# DS131-1_0-ApH.net
KiCad netlist of a schematic drawn in Altium Designer
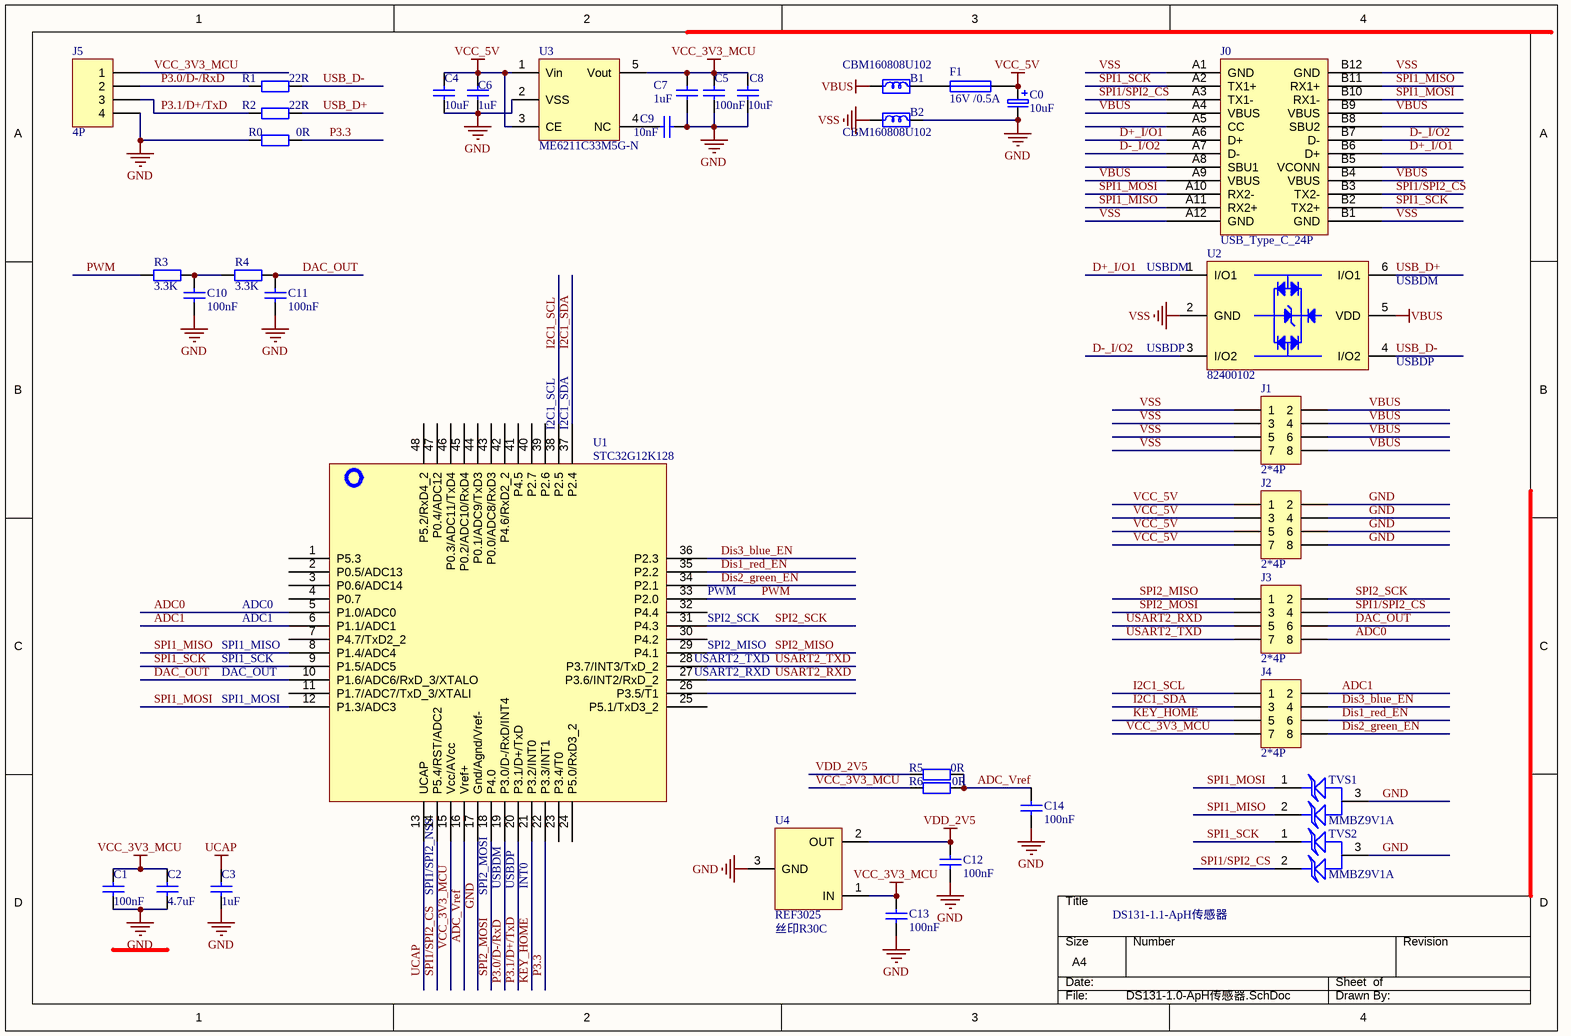
[diagram p0: DS131-1.0-ApH传感器.SchDoc]

(export (version "E")
  (design (tool "Eeschema 10.0.6"))
  (components
    (comp (ref "B1")
      (value "CBM160808U102")
      (footprint "0603Bead")
      (description "贴片磁珠")
      (libsource (lib "AD_SCH") (part "Chip Ferrite Bead 0606"))
    )
    (comp (ref "B2")
      (value "CBM160808U102")
      (footprint "0603Bead")
      (description "贴片磁珠")
      (libsource (lib "AD_SCH") (part "Chip Ferrite Bead 0606"))
    )
    (comp (ref "C0")
      (value "10uF")
      (footprint "AVX_3216-18(1206)_SMD")
      (description "钽电容")
      (fields (field (name "Comment") "AVX_10uF/16V ±10％(C106)"))
      (libsource (lib "AD_SCH") (part "AVX_10uF/16V ±10％(C106)"))
    )
    (comp (ref "C1")
      (value "100nF")
      (footprint "0603CAP")
      (description "贴片电容")
      (fields (field (name "Comment") "SMDCAP00013"))
      (libsource (lib "AD_SCH") (part "MLCC 100nF 50V ±10％ 0603"))
    )
    (comp (ref "C2")
      (value "4.7uF")
      (footprint "0603CAP")
      (description "贴片电容")
      (fields (field (name "Comment") "SMDCAP00012"))
      (libsource (lib "AD_SCH") (part "MLCC 4.7uF 50V ±10％ 0603"))
    )
    (comp (ref "C3")
      (value "1uF")
      (footprint "0603CAP")
      (description "贴片电容")
      (fields (field (name "Comment") "SMDCAP00015"))
      (libsource (lib "AD_SCH") (part "MLCC 1uF 50V ±10％ 0603"))
    )
    (comp (ref "C4")
      (value "10uF")
      (footprint "1206CAP")
      (description "贴片电容")
      (fields (field (name "Comment") "MLCC 10uF 50V ±20％ 1206"))
      (libsource (lib "AD_SCH") (part "MLCC 10uF 50V ±20％ 1206"))
    )
    (comp (ref "C5")
      (value "100nF")
      (footprint "0603CAP")
      (description "贴片电容")
      (fields (field (name "Comment") "SMDCAP00013"))
      (libsource (lib "AD_SCH") (part "MLCC 100nF 50V ±10％ 0603"))
    )
    (comp (ref "C6")
      (value "1uF")
      (footprint "0603CAP")
      (description "贴片电容")
      (fields (field (name "Comment") "SMDCAP00015"))
      (libsource (lib "AD_SCH") (part "MLCC 1uF 50V ±10％ 0603"))
    )
    (comp (ref "C7")
      (value "1uF")
      (footprint "0603CAP")
      (description "贴片电容")
      (fields (field (name "Comment") "SMDCAP00015"))
      (libsource (lib "AD_SCH") (part "MLCC 1uF 50V ±10％ 0603"))
    )
    (comp (ref "C8")
      (value "10uF")
      (footprint "1206CAP")
      (description "贴片电容")
      (fields (field (name "Comment") "MLCC 10uF 50V ±20％ 1206"))
      (libsource (lib "AD_SCH") (part "MLCC 10uF 50V ±20％ 1206"))
    )
    (comp (ref "C9")
      (value "10nF")
      (footprint "0603CAP")
      (description "贴片电容")
      (fields (field (name "Comment") "SMDCAP00010"))
      (libsource (lib "AD_SCH") (part "MLCC 10nF 50V ±10％ 0603"))
    )
    (comp (ref "C10")
      (value "100nF")
      (footprint "0603CAP")
      (description "贴片电容")
      (fields (field (name "Comment") "SMDCAP00013"))
      (libsource (lib "AD_SCH") (part "MLCC 100nF 50V ±10％ 0603"))
    )
    (comp (ref "C11")
      (value "100nF")
      (footprint "0603CAP")
      (description "贴片电容")
      (fields (field (name "Comment") "SMDCAP00013"))
      (libsource (lib "AD_SCH") (part "MLCC 100nF 50V ±10％ 0603"))
    )
    (comp (ref "C12")
      (value "100nF")
      (footprint "0603CAP")
      (description "贴片电容")
      (fields (field (name "Comment") "SMDCAP00013"))
      (libsource (lib "AD_SCH") (part "MLCC 100nF 50V ±10％ 0603"))
    )
    (comp (ref "C13")
      (value "100nF")
      (footprint "0603CAP")
      (description "贴片电容")
      (fields (field (name "Comment") "SMDCAP00013"))
      (libsource (lib "AD_SCH") (part "MLCC 100nF 50V ±10％ 0603"))
    )
    (comp (ref "C14")
      (value "100nF")
      (footprint "0603CAP")
      (description "贴片电容")
      (fields (field (name "Comment") "SMDCAP00013"))
      (libsource (lib "AD_SCH") (part "MLCC 100nF 50V ±10％ 0603"))
    )
    (comp (ref "F1")
      (value "16V /0.5A")
      (footprint "1206FUSE")
      (description "贴片自恢复保险丝 16V /0.5A")
      (fields (field (name "Comment") "SMD1206-050C-16V"))
      (libsource (lib "AD_SCH") (part "SMD1206-050C-16V"))
    )
    (comp (ref "J0")
      (value "USB_Type_C_24P")
      (footprint "USB_TYPE_C_24P_Receptacle")
      (libsource (lib "AD_SCH") (part "USB_Type_C_24P"))
    )
    (comp (ref "J1")
      (value "2*4P")
      (footprint "X1321FVS-2x04-C43D48")
      (description "双排母2x4P 立贴 1.27mm")
      (fields (field (name "Comment") "X1321FVS-2x04-C43D48"))
      (libsource (lib "AD_SCH") (part "X1321FVS-2x04-C43D48"))
    )
    (comp (ref "J2")
      (value "2*4P")
      (footprint "X1321FVS-2x04-C43D48")
      (description "双排母2x4P 立贴 1.27mm")
      (fields (field (name "Comment") "X1321FVS-2x04-C43D48"))
      (libsource (lib "AD_SCH") (part "X1321FVS-2x04-C43D48"))
    )
    (comp (ref "J3")
      (value "2*4P")
      (footprint "X1321FVS-2x04-C43D48")
      (description "双排母2x4P 立贴 1.27mm")
      (fields (field (name "Comment") "X1321FVS-2x04-C43D48"))
      (libsource (lib "AD_SCH") (part "X1321FVS-2x04-C43D48"))
    )
    (comp (ref "J4")
      (value "2*4P")
      (footprint "X1321FVS-2x04-C43D48")
      (description "双排母2x4P 立贴 1.27mm")
      (fields (field (name "Comment") "X1321FVS-2x04-C43D48"))
      (libsource (lib "AD_SCH") (part "X1321FVS-2x04-C43D48"))
    )
    (comp (ref "J5")
      (value "4P")
      (footprint "H4")
      (description "单排直针")
      (fields (field (name "Comment") "DIP4单排直针  间距2mm 针长11mm 铜"))
      (libsource (lib "AD_SCH") (part "DIP4单排直针  间距2mm 针长11mm 铜"))
    )
    (comp (ref "R0")
      (value "0R")
      (footprint "0603RES")
      (description "贴片电阻")
      (fields (field (name "Comment") "Chip 0R 1/16W ±1％ 0603"))
      (libsource (lib "AD_SCH") (part "Chip 0R 1/16W ±1％ 0603"))
    )
    (comp (ref "R1")
      (value "22R")
      (footprint "0603RES")
      (description "贴片电阻")
      (fields (field (name "Comment") "Chip 22R 1/16W ±1％ 0603"))
      (libsource (lib "AD_SCH") (part "Chip 22R 1/16W ±1％ 0603"))
    )
    (comp (ref "R2")
      (value "22R")
      (footprint "0603RES")
      (description "贴片电阻")
      (fields (field (name "Comment") "Chip 22R 1/16W ±1％ 0603"))
      (libsource (lib "AD_SCH") (part "Chip 22R 1/16W ±1％ 0603"))
    )
    (comp (ref "R3")
      (value "3.3K")
      (footprint "0603RES")
      (description "贴片电阻")
      (fields (field (name "Comment") "SMDRES00090"))
      (libsource (lib "AD_SCH") (part "Chip 3.3K 1/16W ±1％ 0603"))
    )
    (comp (ref "R4")
      (value "3.3K")
      (footprint "0603RES")
      (description "贴片电阻")
      (fields (field (name "Comment") "SMDRES00090"))
      (libsource (lib "AD_SCH") (part "Chip 3.3K 1/16W ±1％ 0603"))
    )
    (comp (ref "R5")
      (value "0R")
      (footprint "0603RES")
      (description "贴片电阻")
      (fields (field (name "Comment") "Chip 0R 1/16W ±1％ 0603"))
      (libsource (lib "AD_SCH") (part "Chip 0R 1/16W ±1％ 0603"))
    )
    (comp (ref "R6")
      (value "0R")
      (footprint "0603RES")
      (description "贴片电阻")
      (fields (field (name "Comment") "Chip 0R 1/16W ±1％ 0603"))
      (libsource (lib "AD_SCH") (part "Chip 0R 1/16W ±1％ 0603"))
    )
    (comp (ref "TVS1")
      (value "MMBZ9V1A")
      (footprint "SOT23")
      (description "瞬态抑制二极管")
      (libsource (lib "AD_SCH") (part "TVS"))
    )
    (comp (ref "TVS2")
      (value "MMBZ9V1A")
      (footprint "SOT23")
      (description "瞬态抑制二极管")
      (libsource (lib "AD_SCH") (part "TVS"))
    )
    (comp (ref "U1")
      (value "STC32G12K128")
      (footprint "LQFP-48")
      (description "单片机芯片")
      (fields (field (name "Comment") "STC32G12K128_35I LQFP48"))
      (libsource (lib "AD_SCH") (part "STC32G12K128_35I LQFP48"))
    )
    (comp (ref "U2")
      (value "82400102")
      (footprint "SOT23-6")
      (description "瞬态抑制二极管(TVS)")
      (libsource (lib "AD_SCH") (part "82400102"))
    )
    (comp (ref "U3")
      (value "ME6211C33M5G-N")
      (footprint "SOT23-5")
      (description "稳压芯片")
      (libsource (lib "AD_SCH") (part "ME6211C33M5G-N"))
    )
    (comp (ref "U4")
      (value "REF3025")
      (footprint "SOT23")
      (fields (field (name "ALTIUM_VALUE") "丝印R30C"))
      (libsource (lib "AD_SCH") (part "REF3025"))
    )
  )
  (nets
    (net (code "1") (name "/ADC0") (class "Default")
      (node (ref "J3") (pin "8") (pinfunction "8_8") (pintype "passive"))
      (node (ref "U1") (pin "5") (pinfunction "P1.0/ADC0_5") (pintype "passive"))
    )
    (net (code "2") (name "/ADC1") (class "Default")
      (node (ref "J4") (pin "2") (pinfunction "2_2") (pintype "passive"))
      (node (ref "U1") (pin "6") (pinfunction "P1.1/ADC1_6") (pintype "passive"))
    )
    (net (code "3") (name "/ADC_Vref") (class "Default")
      (node (ref "C14") (pin "2") (pinfunction "2_2") (pintype "passive"))
      (node (ref "R5") (pin "2") (pinfunction "2_2") (pintype "passive"))
      (node (ref "R6") (pin "2") (pinfunction "2_2") (pintype "passive"))
      (node (ref "U1") (pin "16") (pinfunction "Vref+_16") (pintype "passive"))
    )
    (net (code "4") (name "/D+_I{slash}O1") (class "Default")
      (node (ref "J0") (pin "A6") (pinfunction "D+_A6") (pintype "passive"))
      (node (ref "J0") (pin "B6") (pinfunction "D+_B6") (pintype "passive"))
      (node (ref "U2") (pin "1") (pinfunction "I/O1_1") (pintype "passive"))
    )
    (net (code "5") (name "/D-_I{slash}O2") (class "Default")
      (node (ref "J0") (pin "A7") (pinfunction "D-_A7") (pintype "passive"))
      (node (ref "J0") (pin "B7") (pinfunction "D-_B7") (pintype "passive"))
      (node (ref "U2") (pin "3") (pinfunction "I/O2_3") (pintype "passive"))
    )
    (net (code "6") (name "/DAC_OUT") (class "Default")
      (node (ref "C11") (pin "2") (pinfunction "2_2") (pintype "passive"))
      (node (ref "J3") (pin "6") (pinfunction "6_6") (pintype "passive"))
      (node (ref "R4") (pin "2") (pinfunction "2_2") (pintype "passive"))
      (node (ref "U1") (pin "10") (pinfunction "P1.6/ADC6/RxD_3/XTALO_10") (pintype "passive"))
    )
    (net (code "7") (name "/Dis1_red_EN") (class "Default")
      (node (ref "J4") (pin "6") (pinfunction "6_6") (pintype "passive"))
      (node (ref "U1") (pin "35") (pinfunction "P2.2_35") (pintype "passive"))
    )
    (net (code "8") (name "/Dis2_green_EN") (class "Default")
      (node (ref "J4") (pin "8") (pinfunction "8_8") (pintype "passive"))
      (node (ref "U1") (pin "34") (pinfunction "P2.1_34") (pintype "passive"))
    )
    (net (code "9") (name "/Dis3_blue_EN") (class "Default")
      (node (ref "J4") (pin "4") (pinfunction "4_4") (pintype "passive"))
      (node (ref "U1") (pin "36") (pinfunction "P2.3_36") (pintype "passive"))
    )
    (net (code "10") (name "/I2C1_SCL") (class "Default")
      (node (ref "J4") (pin "1") (pinfunction "1_1") (pintype "passive"))
      (node (ref "U1") (pin "38") (pinfunction "P2.5_38") (pintype "passive"))
    )
    (net (code "11") (name "/I2C1_SDA") (class "Default")
      (node (ref "J4") (pin "3") (pinfunction "3_3") (pintype "passive"))
      (node (ref "U1") (pin "37") (pinfunction "P2.4_37") (pintype "passive"))
    )
    (net (code "12") (name "/KEY_HOME") (class "Default")
      (node (ref "J4") (pin "5") (pinfunction "5_5") (pintype "passive"))
      (node (ref "U1") (pin "21") (pinfunction "P3.2/INT0_21") (pintype "passive"))
    )
    (net (code "13") (name "/P3.0{slash}D-{slash}RxD") (class "Default")
      (node (ref "J5") (pin "2") (pinfunction "2_2") (pintype "passive"))
      (node (ref "R1") (pin "1") (pinfunction "1_1") (pintype "passive"))
      (node (ref "U1") (pin "19") (pinfunction "P3.0/D-/RxD/INT4_19") (pintype "passive"))
    )
    (net (code "14") (name "/P3.1{slash}D+{slash}TxD") (class "Default")
      (node (ref "J5") (pin "3") (pinfunction "3_3") (pintype "passive"))
      (node (ref "R2") (pin "1") (pinfunction "1_1") (pintype "passive"))
      (node (ref "U1") (pin "20") (pinfunction "P3.1/D+/TxD_20") (pintype "passive"))
    )
    (net (code "15") (name "/P3.3") (class "Default")
      (node (ref "R0") (pin "2") (pinfunction "2_2") (pintype "passive"))
      (node (ref "U1") (pin "22") (pinfunction "P3.3/INT1_22") (pintype "passive"))
    )
    (net (code "16") (name "/PWM") (class "Default")
      (node (ref "R3") (pin "1") (pinfunction "1_1") (pintype "passive"))
      (node (ref "U1") (pin "33") (pinfunction "P2.0_33") (pintype "passive"))
    )
    (net (code "17") (name "/SPI1_MISO") (class "Default")
      (node (ref "J0") (pin "A11") (pinfunction "RX2+_A11") (pintype "passive"))
      (node (ref "J0") (pin "B11") (pinfunction "RX1+_B11") (pintype "passive"))
      (node (ref "TVS1") (pin "2") (pinfunction "2_2") (pintype "passive"))
      (node (ref "U1") (pin "8") (pinfunction "P1.4/ADC4_8") (pintype "passive"))
    )
    (net (code "18") (name "/SPI1_MOSI") (class "Default")
      (node (ref "J0") (pin "A10") (pinfunction "RX2-_A10") (pintype "passive"))
      (node (ref "J0") (pin "B10") (pinfunction "RX1-_B10") (pintype "passive"))
      (node (ref "TVS1") (pin "1") (pinfunction "1_1") (pintype "passive"))
      (node (ref "U1") (pin "12") (pinfunction "P1.3/ADC3_12") (pintype "passive"))
    )
    (net (code "19") (name "/SPI1_SCK") (class "Default")
      (node (ref "J0") (pin "A2") (pinfunction "TX1+_A2") (pintype "passive"))
      (node (ref "J0") (pin "B2") (pinfunction "TX2+_B2") (pintype "passive"))
      (node (ref "TVS2") (pin "1") (pinfunction "1_1") (pintype "passive"))
      (node (ref "U1") (pin "9") (pinfunction "P1.5/ADC5_9") (pintype "passive"))
    )
    (net (code "20") (name "/SPI1{slash}SPI2_CS") (class "Default")
      (node (ref "J0") (pin "A3") (pinfunction "TX1-_A3") (pintype "passive"))
      (node (ref "J0") (pin "B3") (pinfunction "TX2-_B3") (pintype "passive"))
      (node (ref "J3") (pin "4") (pinfunction "4_4") (pintype "passive"))
      (node (ref "TVS2") (pin "2") (pinfunction "2_2") (pintype "passive"))
      (node (ref "U1") (pin "14") (pinfunction "P5.4/RST/ADC2_14") (pintype "passive"))
    )
    (net (code "21") (name "/SPI2_MISO") (class "Default")
      (node (ref "J3") (pin "1") (pinfunction "1_1") (pintype "passive"))
      (node (ref "U1") (pin "29") (pinfunction "P4.1_29") (pintype "passive"))
    )
    (net (code "22") (name "/SPI2_MOSI") (class "Default")
      (node (ref "J3") (pin "3") (pinfunction "3_3") (pintype "passive"))
      (node (ref "U1") (pin "18") (pinfunction "P4.0_18") (pintype "passive"))
    )
    (net (code "23") (name "/SPI2_SCK") (class "Default")
      (node (ref "J3") (pin "2") (pinfunction "2_2") (pintype "passive"))
      (node (ref "U1") (pin "31") (pinfunction "P4.3_31") (pintype "passive"))
    )
    (net (code "24") (name "/USART2_RXD") (class "Default")
      (node (ref "J3") (pin "5") (pinfunction "5_5") (pintype "passive"))
      (node (ref "U1") (pin "27") (pinfunction "P3.6/INT2/RxD_2_27") (pintype "passive"))
    )
    (net (code "25") (name "/USART2_TXD") (class "Default")
      (node (ref "J3") (pin "7") (pinfunction "7_7") (pintype "passive"))
      (node (ref "U1") (pin "28") (pinfunction "P3.7/INT3/TxD_2_28") (pintype "passive"))
    )
    (net (code "26") (name "/USB_D+") (class "Default")
      (node (ref "R2") (pin "2") (pinfunction "2_2") (pintype "passive"))
      (node (ref "U2") (pin "6") (pinfunction "I/O1_6") (pintype "passive"))
    )
    (net (code "27") (name "/USB_D-") (class "Default")
      (node (ref "R1") (pin "2") (pinfunction "2_2") (pintype "passive"))
      (node (ref "U2") (pin "4") (pinfunction "I/O2_4") (pintype "passive"))
    )
    (net (code "28") (name "GND") (class "Default")
      (node (ref "B2") (pin "2") (pinfunction "2_2") (pintype "passive"))
      (node (ref "C0") (pin "2") (pinfunction "2_2") (pintype "passive"))
      (node (ref "C1") (pin "1") (pinfunction "1_1") (pintype "passive"))
      (node (ref "C10") (pin "1") (pinfunction "1_1") (pintype "passive"))
      (node (ref "C11") (pin "1") (pinfunction "1_1") (pintype "passive"))
      (node (ref "C12") (pin "1") (pinfunction "1_1") (pintype "passive"))
      (node (ref "C13") (pin "1") (pinfunction "1_1") (pintype "passive"))
      (node (ref "C14") (pin "1") (pinfunction "1_1") (pintype "passive"))
      (node (ref "C2") (pin "1") (pinfunction "1_1") (pintype "passive"))
      (node (ref "C3") (pin "1") (pinfunction "1_1") (pintype "passive"))
      (node (ref "C4") (pin "1") (pinfunction "1_1") (pintype "passive"))
      (node (ref "C5") (pin "1") (pinfunction "1_1") (pintype "passive"))
      (node (ref "C6") (pin "1") (pinfunction "1_1") (pintype "passive"))
      (node (ref "C7") (pin "1") (pinfunction "1_1") (pintype "passive"))
      (node (ref "C8") (pin "1") (pinfunction "1_1") (pintype "passive"))
      (node (ref "C9") (pin "2") (pinfunction "2_2") (pintype "passive"))
      (node (ref "J2") (pin "2") (pinfunction "2_2") (pintype "passive"))
      (node (ref "J2") (pin "4") (pinfunction "4_4") (pintype "passive"))
      (node (ref "J2") (pin "6") (pinfunction "6_6") (pintype "passive"))
      (node (ref "J2") (pin "8") (pinfunction "8_8") (pintype "passive"))
      (node (ref "J5") (pin "4") (pinfunction "4_4") (pintype "passive"))
      (node (ref "R0") (pin "1") (pinfunction "1_1") (pintype "passive"))
      (node (ref "TVS1") (pin "3") (pinfunction "3_3") (pintype "passive"))
      (node (ref "TVS2") (pin "3") (pinfunction "3_3") (pintype "passive"))
      (node (ref "U1") (pin "17") (pinfunction "Gnd/Agnd/Vref-_17") (pintype "passive"))
      (node (ref "U3") (pin "2") (pinfunction "VSS_2") (pintype "passive"))
      (node (ref "U4") (pin "3") (pinfunction "GND_3") (pintype "passive"))
    )
    (net (code "29") (name "Net-(B1-Pad2)") (class "Default")
      (node (ref "B1") (pin "2") (pinfunction "2_2") (pintype "passive"))
      (node (ref "F1") (pin "1") (pinfunction "1_1") (pintype "passive"))
    )
    (net (code "30") (name "Net-(C10-Pad2)") (class "Default")
      (node (ref "C10") (pin "2") (pinfunction "2_2") (pintype "passive"))
      (node (ref "R3") (pin "2") (pinfunction "2_2") (pintype "passive"))
      (node (ref "R4") (pin "1") (pinfunction "1_1") (pintype "passive"))
    )
    (net (code "31") (name "Net-(U3-NC)") (class "Default")
      (node (ref "C9") (pin "1") (pinfunction "1_1") (pintype "passive"))
      (node (ref "U3") (pin "4") (pinfunction "NC_4") (pintype "passive"))
    )
    (net (code "32") (name "UCAP") (class "Default")
      (node (ref "C3") (pin "2") (pinfunction "2_2") (pintype "passive"))
      (node (ref "U1") (pin "13") (pinfunction "UCAP_13") (pintype "passive"))
    )
    (net (code "33") (name "VBUS") (class "Default")
      (node (ref "B1") (pin "1") (pinfunction "1_1") (pintype "passive"))
      (node (ref "J0") (pin "A4") (pinfunction "VBUS_A4") (pintype "passive"))
      (node (ref "J0") (pin "A9") (pinfunction "VBUS_A9") (pintype "passive"))
      (node (ref "J0") (pin "B4") (pinfunction "VBUS_B4") (pintype "passive"))
      (node (ref "J0") (pin "B9") (pinfunction "VBUS_B9") (pintype "passive"))
      (node (ref "J1") (pin "2") (pinfunction "2_2") (pintype "passive"))
      (node (ref "J1") (pin "4") (pinfunction "4_4") (pintype "passive"))
      (node (ref "J1") (pin "6") (pinfunction "6_6") (pintype "passive"))
      (node (ref "J1") (pin "8") (pinfunction "8_8") (pintype "passive"))
      (node (ref "U2") (pin "5") (pinfunction "VDD_5") (pintype "passive"))
    )
    (net (code "34") (name "VCC_3V3_MCU") (class "Default")
      (node (ref "C1") (pin "2") (pinfunction "2_2") (pintype "passive"))
      (node (ref "C13") (pin "2") (pinfunction "2_2") (pintype "passive"))
      (node (ref "C2") (pin "2") (pinfunction "2_2") (pintype "passive"))
      (node (ref "C5") (pin "2") (pinfunction "2_2") (pintype "passive"))
      (node (ref "C7") (pin "2") (pinfunction "2_2") (pintype "passive"))
      (node (ref "C8") (pin "2") (pinfunction "2_2") (pintype "passive"))
      (node (ref "J4") (pin "7") (pinfunction "7_7") (pintype "passive"))
      (node (ref "J5") (pin "1") (pinfunction "1_1") (pintype "passive"))
      (node (ref "R6") (pin "1") (pinfunction "1_1") (pintype "passive"))
      (node (ref "U1") (pin "15") (pinfunction "Vcc/AVcc_15") (pintype "passive"))
      (node (ref "U3") (pin "5") (pinfunction "Vout_5") (pintype "passive"))
      (node (ref "U4") (pin "1") (pinfunction "IN_1") (pintype "passive"))
    )
    (net (code "35") (name "VCC_5V") (class "Default")
      (node (ref "C0") (pin "1") (pinfunction "1_1") (pintype "passive"))
      (node (ref "C4") (pin "2") (pinfunction "2_2") (pintype "passive"))
      (node (ref "C6") (pin "2") (pinfunction "2_2") (pintype "passive"))
      (node (ref "F1") (pin "2") (pinfunction "2_2") (pintype "passive"))
      (node (ref "J2") (pin "1") (pinfunction "1_1") (pintype "passive"))
      (node (ref "J2") (pin "3") (pinfunction "3_3") (pintype "passive"))
      (node (ref "J2") (pin "5") (pinfunction "5_5") (pintype "passive"))
      (node (ref "J2") (pin "7") (pinfunction "7_7") (pintype "passive"))
      (node (ref "U3") (pin "1") (pinfunction "Vin_1") (pintype "passive"))
      (node (ref "U3") (pin "3") (pinfunction "CE_3") (pintype "passive"))
    )
    (net (code "36") (name "VDD_2V5") (class "Default")
      (node (ref "C12") (pin "2") (pinfunction "2_2") (pintype "passive"))
      (node (ref "R5") (pin "1") (pinfunction "1_1") (pintype "passive"))
      (node (ref "U4") (pin "2") (pinfunction "OUT_2") (pintype "passive"))
    )
    (net (code "37") (name "VSS") (class "Default")
      (node (ref "B2") (pin "1") (pinfunction "1_1") (pintype "passive"))
      (node (ref "J0") (pin "A1") (pinfunction "GND_A1") (pintype "passive"))
      (node (ref "J0") (pin "A12") (pinfunction "GND_A12") (pintype "passive"))
      (node (ref "J0") (pin "B1") (pinfunction "GND_B1") (pintype "passive"))
      (node (ref "J0") (pin "B12") (pinfunction "GND_B12") (pintype "passive"))
      (node (ref "J1") (pin "1") (pinfunction "1_1") (pintype "passive"))
      (node (ref "J1") (pin "3") (pinfunction "3_3") (pintype "passive"))
      (node (ref "J1") (pin "5") (pinfunction "5_5") (pintype "passive"))
      (node (ref "J1") (pin "7") (pinfunction "7_7") (pintype "passive"))
      (node (ref "U2") (pin "2") (pinfunction "GND_2") (pintype "passive"))
    )
    (net (code "38") (name "unconnected-(J0-CC-PadA5)") (class "Default")
      (node (ref "J0") (pin "A5") (pinfunction "CC_A5") (pintype "passive"))
    )
    (net (code "39") (name "unconnected-(J0-SBU1-PadA8)") (class "Default")
      (node (ref "J0") (pin "A8") (pinfunction "SBU1_A8") (pintype "passive"))
    )
    (net (code "40") (name "unconnected-(J0-SBU2-PadB8)") (class "Default")
      (node (ref "J0") (pin "B8") (pinfunction "SBU2_B8") (pintype "passive"))
    )
    (net (code "41") (name "unconnected-(J0-VCONN-PadB5)") (class "Default")
      (node (ref "J0") (pin "B5") (pinfunction "VCONN_B5") (pintype "passive"))
    )
    (net (code "42") (name "unconnected-(U1-P0.0{slash}ADC8{slash}RxD3-Pad43)") (class "Default")
      (node (ref "U1") (pin "43") (pinfunction "P0.0/ADC8/RxD3_43") (pintype "passive"))
    )
    (net (code "43") (name "unconnected-(U1-P0.1{slash}ADC9{slash}TxD3-Pad44)") (class "Default")
      (node (ref "U1") (pin "44") (pinfunction "P0.1/ADC9/TxD3_44") (pintype "passive"))
    )
    (net (code "44") (name "unconnected-(U1-P0.2{slash}ADC10{slash}RxD4-Pad45)") (class "Default")
      (node (ref "U1") (pin "45") (pinfunction "P0.2/ADC10/RxD4_45") (pintype "passive"))
    )
    (net (code "45") (name "unconnected-(U1-P0.3{slash}ADC11{slash}TxD4-Pad46)") (class "Default")
      (node (ref "U1") (pin "46") (pinfunction "P0.3/ADC11/TxD4_46") (pintype "passive"))
    )
    (net (code "46") (name "unconnected-(U1-P0.4{slash}ADC12-Pad47)") (class "Default")
      (node (ref "U1") (pin "47") (pinfunction "P0.4/ADC12_47") (pintype "passive"))
    )
    (net (code "47") (name "unconnected-(U1-P0.5{slash}ADC13-Pad2)") (class "Default")
      (node (ref "U1") (pin "2") (pinfunction "P0.5/ADC13_2") (pintype "passive"))
    )
    (net (code "48") (name "unconnected-(U1-P0.6{slash}ADC14-Pad3)") (class "Default")
      (node (ref "U1") (pin "3") (pinfunction "P0.6/ADC14_3") (pintype "passive"))
    )
    (net (code "49") (name "unconnected-(U1-P0.7-Pad4)") (class "Default")
      (node (ref "U1") (pin "4") (pinfunction "P0.7_4") (pintype "passive"))
    )
    (net (code "50") (name "unconnected-(U1-P1.7{slash}ADC7{slash}TxD_3{slash}XTALI-Pad11)") (class "Default")
      (node (ref "U1") (pin "11") (pinfunction "P1.7/ADC7/TxD_3/XTALI_11") (pintype "passive"))
    )
    (net (code "51") (name "unconnected-(U1-P2.6-Pad39)") (class "Default")
      (node (ref "U1") (pin "39") (pinfunction "P2.6_39") (pintype "passive"))
    )
    (net (code "52") (name "unconnected-(U1-P2.7-Pad40)") (class "Default")
      (node (ref "U1") (pin "40") (pinfunction "P2.7_40") (pintype "passive"))
    )
    (net (code "53") (name "unconnected-(U1-P3.4{slash}T0-Pad23)") (class "Default")
      (node (ref "U1") (pin "23") (pinfunction "P3.4/T0_23") (pintype "passive"))
    )
    (net (code "54") (name "unconnected-(U1-P3.5{slash}T1-Pad26)") (class "Default")
      (node (ref "U1") (pin "26") (pinfunction "P3.5/T1_26") (pintype "passive"))
    )
    (net (code "55") (name "unconnected-(U1-P4.2-Pad30)") (class "Default")
      (node (ref "U1") (pin "30") (pinfunction "P4.2_30") (pintype "passive"))
    )
    (net (code "56") (name "unconnected-(U1-P4.4-Pad32)") (class "Default")
      (node (ref "U1") (pin "32") (pinfunction "P4.4_32") (pintype "passive"))
    )
    (net (code "57") (name "unconnected-(U1-P4.5-Pad41)") (class "Default")
      (node (ref "U1") (pin "41") (pinfunction "P4.5_41") (pintype "passive"))
    )
    (net (code "58") (name "unconnected-(U1-P4.6{slash}RxD2_2-Pad42)") (class "Default")
      (node (ref "U1") (pin "42") (pinfunction "P4.6/RxD2_2_42") (pintype "passive"))
    )
    (net (code "59") (name "unconnected-(U1-P4.7{slash}TxD2_2-Pad7)") (class "Default")
      (node (ref "U1") (pin "7") (pinfunction "P4.7/TxD2_2_7") (pintype "passive"))
    )
    (net (code "60") (name "unconnected-(U1-P5.0{slash}RxD3_2-Pad24)") (class "Default")
      (node (ref "U1") (pin "24") (pinfunction "P5.0/RxD3_2_24") (pintype "passive"))
    )
    (net (code "61") (name "unconnected-(U1-P5.1{slash}TxD3_2-Pad25)") (class "Default")
      (node (ref "U1") (pin "25") (pinfunction "P5.1/TxD3_2_25") (pintype "passive"))
    )
    (net (code "62") (name "unconnected-(U1-P5.2{slash}RxD4_2-Pad48)") (class "Default")
      (node (ref "U1") (pin "48") (pinfunction "P5.2/RxD4_2_48") (pintype "passive"))
    )
    (net (code "63") (name "unconnected-(U1-P5.3-Pad1)") (class "Default")
      (node (ref "U1") (pin "1") (pinfunction "P5.3_1") (pintype "passive"))
    )
  )
)
